# ADG801Inline.net
KiCad netlist of a schematic drawn in EAGLE
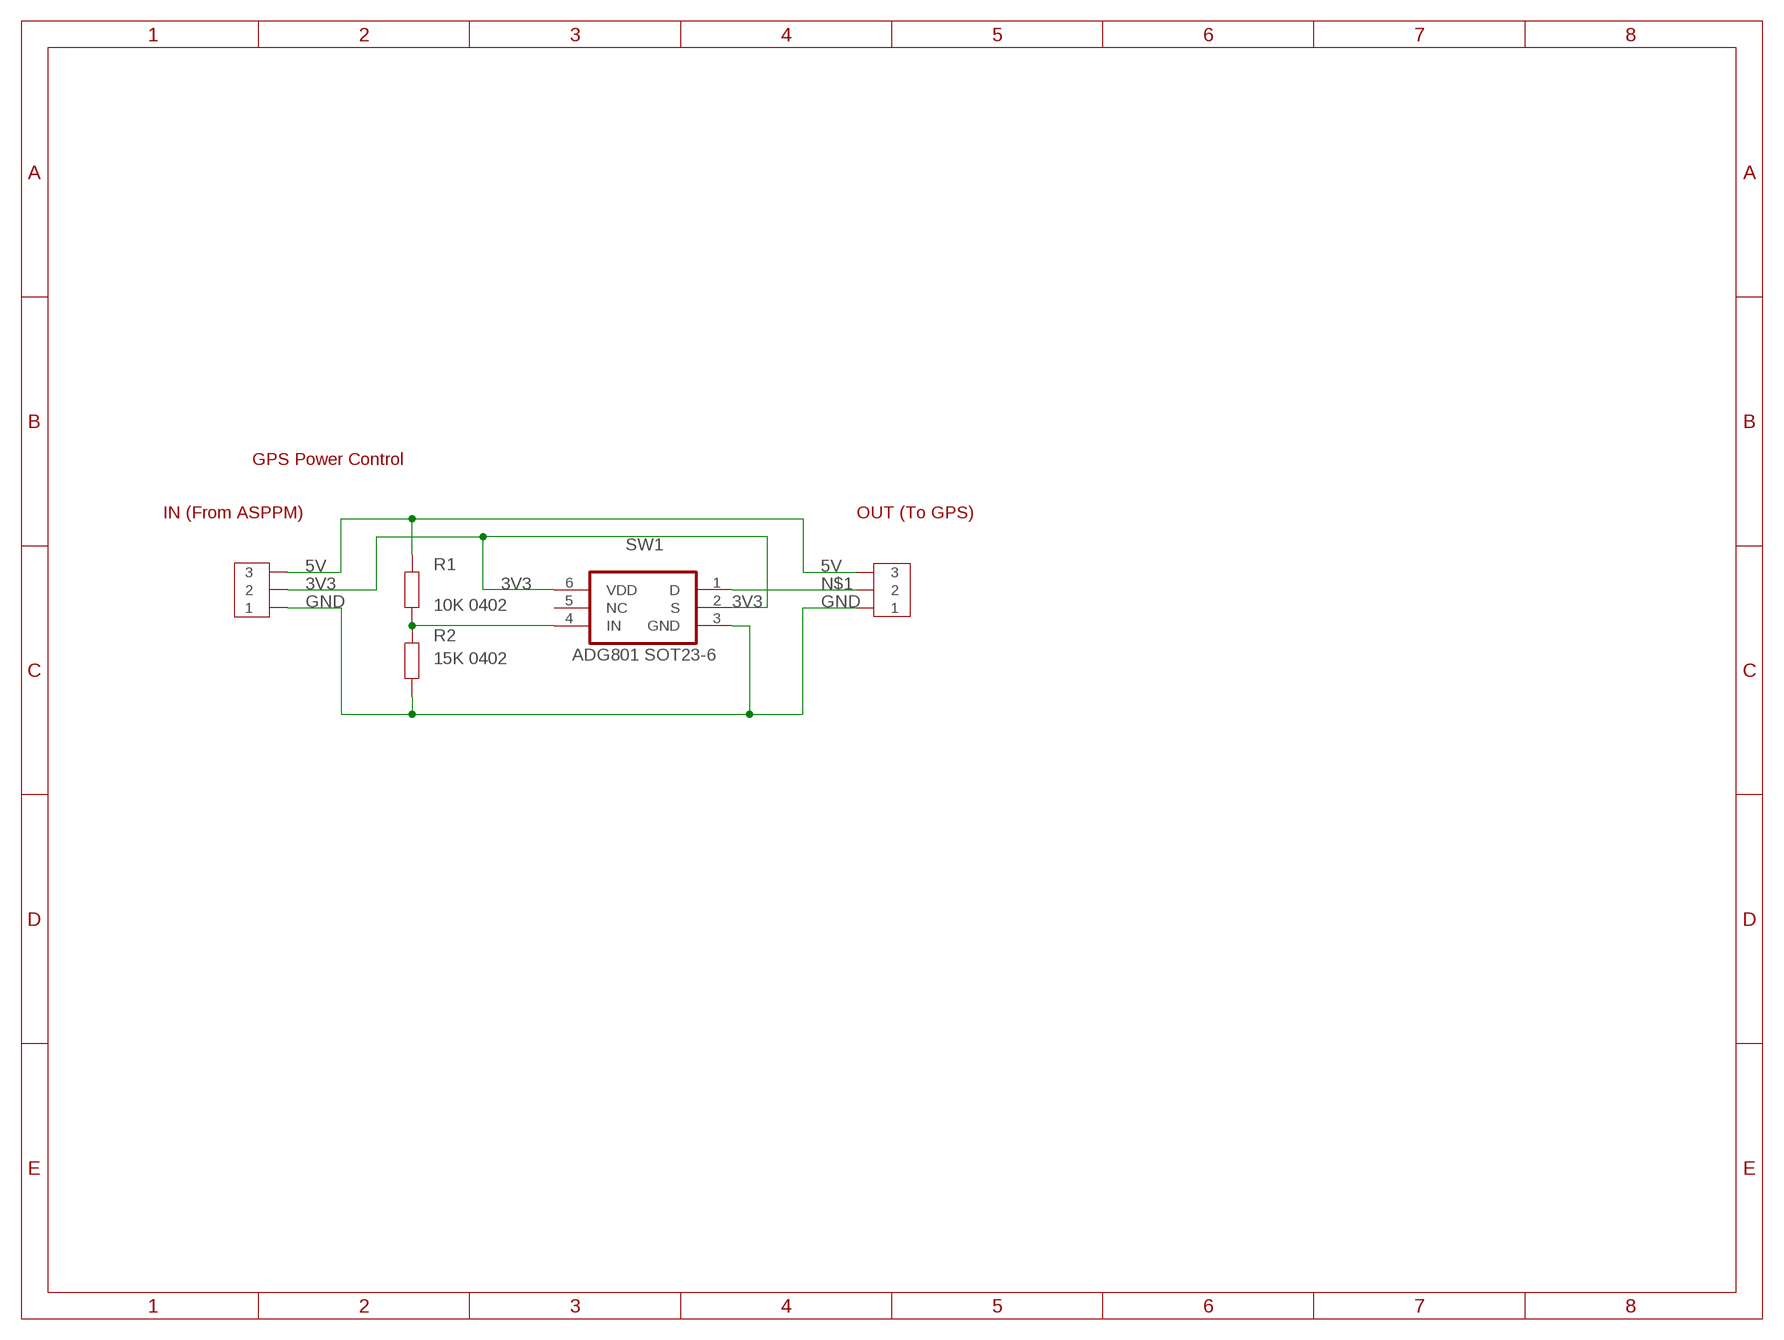
[diagram p0: schematic, sheet 1]

(export (version "E")
  (design (tool "Eeschema 10.0.6"))
  (components
    (comp (ref "JP1")
      (value "3PIN_SMD")
      (footprint "eagle-import:1X3-2MM")
      (libsource (lib "eagle-import") (part "3PIN_SMD"))
    )
    (comp (ref "JP2")
      (value "3PIN_SMD")
      (footprint "eagle-import:1X3-2MM")
      (libsource (lib "eagle-import") (part "3PIN_SMD"))
    )
    (comp (ref "R1")
      (value "10K 0402")
      (footprint "eagle-import:0402")
      (libsource (lib "eagle-import") (part "RESISTOR0402"))
    )
    (comp (ref "R2")
      (value "15K 0402")
      (footprint "eagle-import:0402")
      (libsource (lib "eagle-import") (part "RESISTOR0402"))
    )
    (comp (ref "SW1")
      (value "ADG801 SOT23-6")
      (footprint "eagle-import:SOT23-6")
      (libsource (lib "eagle-import") (part "ADG801SOT23-6"))
    )
  )
  (nets
    (net (code "1") (name "/3V3") (class "Default")
      (node (ref "JP1") (pin "P$2") (pinfunction "2_P$2") (pintype "bidirectional"))
      (node (ref "SW1") (pin "2") (pinfunction "S_2") (pintype "bidirectional"))
      (node (ref "SW1") (pin "6") (pinfunction "VDD_6") (pintype "bidirectional"))
    )
    (net (code "2") (name "/5V") (class "Default")
      (node (ref "JP1") (pin "P$3") (pinfunction "3_P$3") (pintype "bidirectional"))
      (node (ref "JP2") (pin "P$3") (pinfunction "3_P$3") (pintype "bidirectional"))
      (node (ref "R1") (pin "2") (pinfunction "2_2") (pintype "passive"))
    )
    (net (code "3") (name "/GND") (class "Default")
      (node (ref "JP1") (pin "P$1") (pinfunction "1_P$1") (pintype "bidirectional"))
      (node (ref "JP2") (pin "P$1") (pinfunction "1_P$1") (pintype "bidirectional"))
      (node (ref "R2") (pin "1") (pinfunction "1_1") (pintype "passive"))
      (node (ref "SW1") (pin "3") (pinfunction "GND_3") (pintype "bidirectional"))
    )
    (net (code "4") (name "/N$1") (class "Default")
      (node (ref "JP2") (pin "P$2") (pinfunction "2_P$2") (pintype "bidirectional"))
      (node (ref "SW1") (pin "1") (pinfunction "D_1") (pintype "bidirectional"))
    )
    (net (code "5") (name "Net-(SW1-IN)") (class "Default")
      (node (ref "R1") (pin "1") (pinfunction "1_1") (pintype "passive"))
      (node (ref "R2") (pin "2") (pinfunction "2_2") (pintype "passive"))
      (node (ref "SW1") (pin "4") (pinfunction "IN_4") (pintype "bidirectional"))
    )
    (net (code "6") (name "unconnected-(SW1-NC-Pad5)") (class "Default")
      (node (ref "SW1") (pin "5") (pinfunction "NC_5") (pintype "bidirectional"))
    )
  )
)
